# 05_-_Sensors.net
KiCad netlist of a schematic drawn in Altium Designer
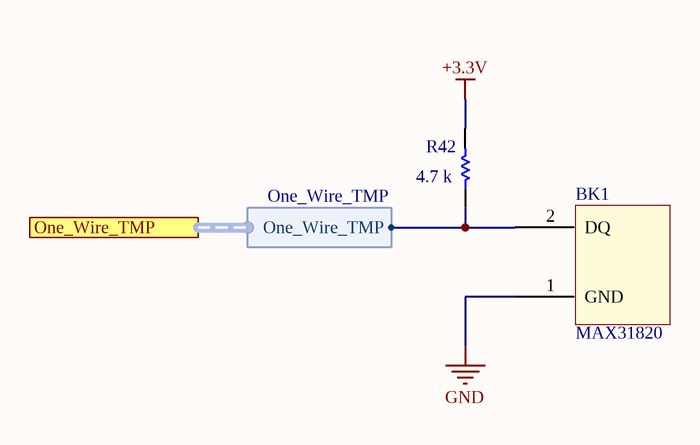
[diagram p0: [05] - Sensors.SchDoc]

(export (version "E")
  (design (tool "Eeschema 10.0.6"))
  (components
    (comp (ref "BK1")
      (value "MAX31820")
      (footprint "TO92127P495H695-3")
      (description "MAX31820PAR  temper sensor")
      (libsource (lib "Blue Tractor-2021") (part "MAX31820"))
    )
    (comp (ref "R42")
      (value "Res1")
      (footprint "Blue Tractor-2021:0603_R")
      (description "Chip Resistor")
      (fields
        (field (name "MANUFACTURER") "Panasonic")
        (field (name "MANUFACTURER PART NUMBER") "ERJ-3GEYJ103V")
        (field (name "RESISTANCE") "4.7 k")
      )
      (libsource (lib "Altium_Library") (part "Res1"))
    )
  )
  (nets
    (net (code "2") (name "+3.3V") (class "Default")
      (node (ref "R42") (pin "2") (pinfunction "2_2") (pintype "passive"))
    )
    (net (code "4") (name "GND") (class "Default")
      (node (ref "BK1") (pin "1") (pinfunction "GND_1") (pintype "power_in"))
    )
    (net (code "5") (name "Net-(BK1-DQ)") (class "Default")
      (node (ref "BK1") (pin "2") (pinfunction "DQ_2") (pintype "power_in"))
      (node (ref "R42") (pin "1") (pinfunction "1_1") (pintype "passive"))
    )
  )
)
